# tesla4x.net
KiCad netlist of a schematic drawn in EAGLE
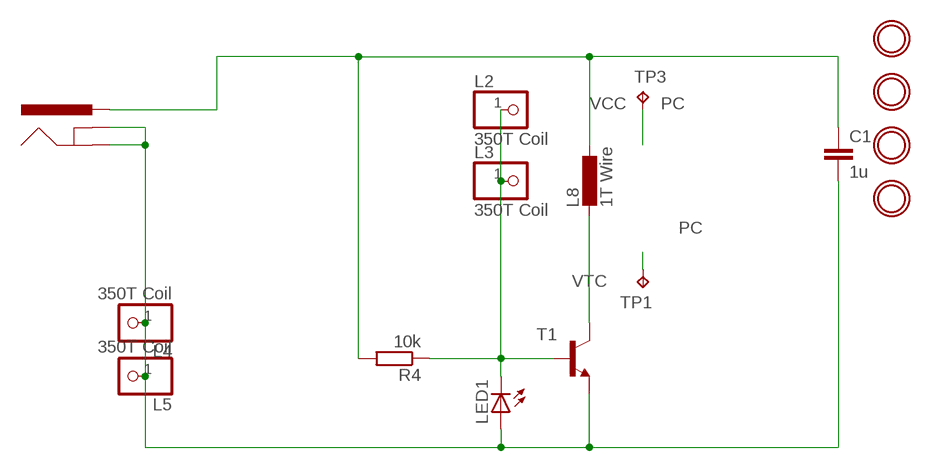
[diagram p0: schematic, sheet 1]

(export (version "E")
  (design (tool "Eeschema 10.0.6"))
  (components
    (comp (ref "C1")
      (value "1u")
      (footprint "eagle-import:C050-025X075")
      (libsource (lib "eagle-import") (part "C-EU050-025X075"))
    )
    (comp (ref "J1")
      (value "POWER_JACKPTH")
      (footprint "eagle-import:POWER_JACK_PTH")
      (libsource (lib "eagle-import") (part "POWER_JACKPTH"))
    )
    (comp (ref "L2")
      (value "350T Coil")
      (footprint "eagle-import:1X01")
      (libsource (lib "eagle-import") (part "PINHD-1X1"))
    )
    (comp (ref "L3")
      (value "350T Coil")
      (footprint "eagle-import:1X01")
      (libsource (lib "eagle-import") (part "PINHD-1X1"))
    )
    (comp (ref "L4")
      (value "350T Coil")
      (footprint "eagle-import:1X01")
      (libsource (lib "eagle-import") (part "PINHD-1X1"))
    )
    (comp (ref "L5")
      (value "350T Coil")
      (footprint "eagle-import:1X01")
      (libsource (lib "eagle-import") (part "PINHD-1X1"))
    )
    (comp (ref "L8")
      (value "1T Wire")
      (footprint "eagle-import:0204_7")
      (libsource (lib "eagle-import") (part "L-EU0204/7"))
    )
    (comp (ref "LED1")
      (value "LED3MM")
      (footprint "eagle-import:LED3MM")
      (libsource (lib "eagle-import") (part "LED3MM"))
    )
    (comp (ref "R4")
      (value "10k")
      (footprint "eagle-import:0207_7")
      (libsource (lib "eagle-import") (part "R-EU_0207/7"))
    )
    (comp (ref "T1")
      (value "-NPN-TO220")
      (footprint "eagle-import:TO220")
      (libsource (lib "eagle-import") (part "-NPN-TO220"))
    )
    (comp (ref "TP1")
      (value "TPTP20SQ")
      (footprint "eagle-import:TP20SQ")
      (libsource (lib "eagle-import") (part "TPTP20SQ"))
    )
    (comp (ref "TP3")
      (value "TPTP20R")
      (footprint "eagle-import:TP20R")
      (libsource (lib "eagle-import") (part "TPTP20R"))
    )
    (comp (ref "U$1")
      (value "MOUNTINGHOLE3.0THIN")
      (footprint "eagle-import:MOUNTINGHOLE_3.0_PLATEDTHIN")
      (libsource (lib "eagle-import") (part "MOUNTINGHOLE3.0THIN"))
    )
    (comp (ref "U$2")
      (value "MOUNTINGHOLE3.0THIN")
      (footprint "eagle-import:MOUNTINGHOLE_3.0_PLATEDTHIN")
      (libsource (lib "eagle-import") (part "MOUNTINGHOLE3.0THIN"))
    )
    (comp (ref "U$3")
      (value "MOUNTINGHOLE3.0THIN")
      (footprint "eagle-import:MOUNTINGHOLE_3.0_PLATEDTHIN")
      (libsource (lib "eagle-import") (part "MOUNTINGHOLE3.0THIN"))
    )
    (comp (ref "U$4")
      (value "MOUNTINGHOLE3.0THIN")
      (footprint "eagle-import:MOUNTINGHOLE_3.0_PLATEDTHIN")
      (libsource (lib "eagle-import") (part "MOUNTINGHOLE3.0THIN"))
    )
  )
  (nets
    (net (code "1") (name "/PC") (class "Default")
      (node (ref "TP1") (pin "TP") (pinfunction "TP_TP") (pintype "input"))
      (node (ref "TP3") (pin "TP") (pinfunction "TP_TP") (pintype "input"))
    )
    (net (code "2") (name "/VCC") (class "Default")
      (node (ref "C1") (pin "1") (pinfunction "1_1") (pintype "passive"))
      (node (ref "J1") (pin "PWR") (pinfunction "PWR_PWR") (pintype "bidirectional"))
      (node (ref "L8") (pin "1") (pinfunction "1_1") (pintype "passive"))
      (node (ref "R4") (pin "2") (pinfunction "2_2") (pintype "passive"))
    )
    (net (code "3") (name "/VTC") (class "Default")
      (node (ref "L8") (pin "2") (pinfunction "2_2") (pintype "passive"))
      (node (ref "T1") (pin "2") (pinfunction "C_2") (pintype "passive"))
    )
    (net (code "4") (name "Net-(LED1-C)") (class "Default")
      (node (ref "L2") (pin "1") (pinfunction "1_1") (pintype "passive"))
      (node (ref "L3") (pin "1") (pinfunction "1_1") (pintype "passive"))
      (node (ref "LED1") (pin "K") (pinfunction "C_K") (pintype "passive"))
      (node (ref "R4") (pin "1") (pinfunction "1_1") (pintype "passive"))
      (node (ref "T1") (pin "1") (pinfunction "B_1") (pintype "passive"))
    )
    (net (code "5") (name "Net-(T1-E)") (class "Default")
      (node (ref "C1") (pin "2") (pinfunction "2_2") (pintype "passive"))
      (node (ref "J1") (pin "GND") (pinfunction "GND_GND") (pintype "bidirectional"))
      (node (ref "J1") (pin "GNDBREAK") (pinfunction "GNDBREAK_GNDBREAK") (pintype "bidirectional"))
      (node (ref "L4") (pin "1") (pinfunction "1_1") (pintype "passive"))
      (node (ref "L5") (pin "1") (pinfunction "1_1") (pintype "passive"))
      (node (ref "LED1") (pin "A") (pinfunction "A_A") (pintype "passive"))
      (node (ref "T1") (pin "3") (pinfunction "E_3") (pintype "passive"))
    )
  )
)
